# Tractive_System_Light_Control_Board.net
KiCad netlist of a schematic drawn in EAGLE
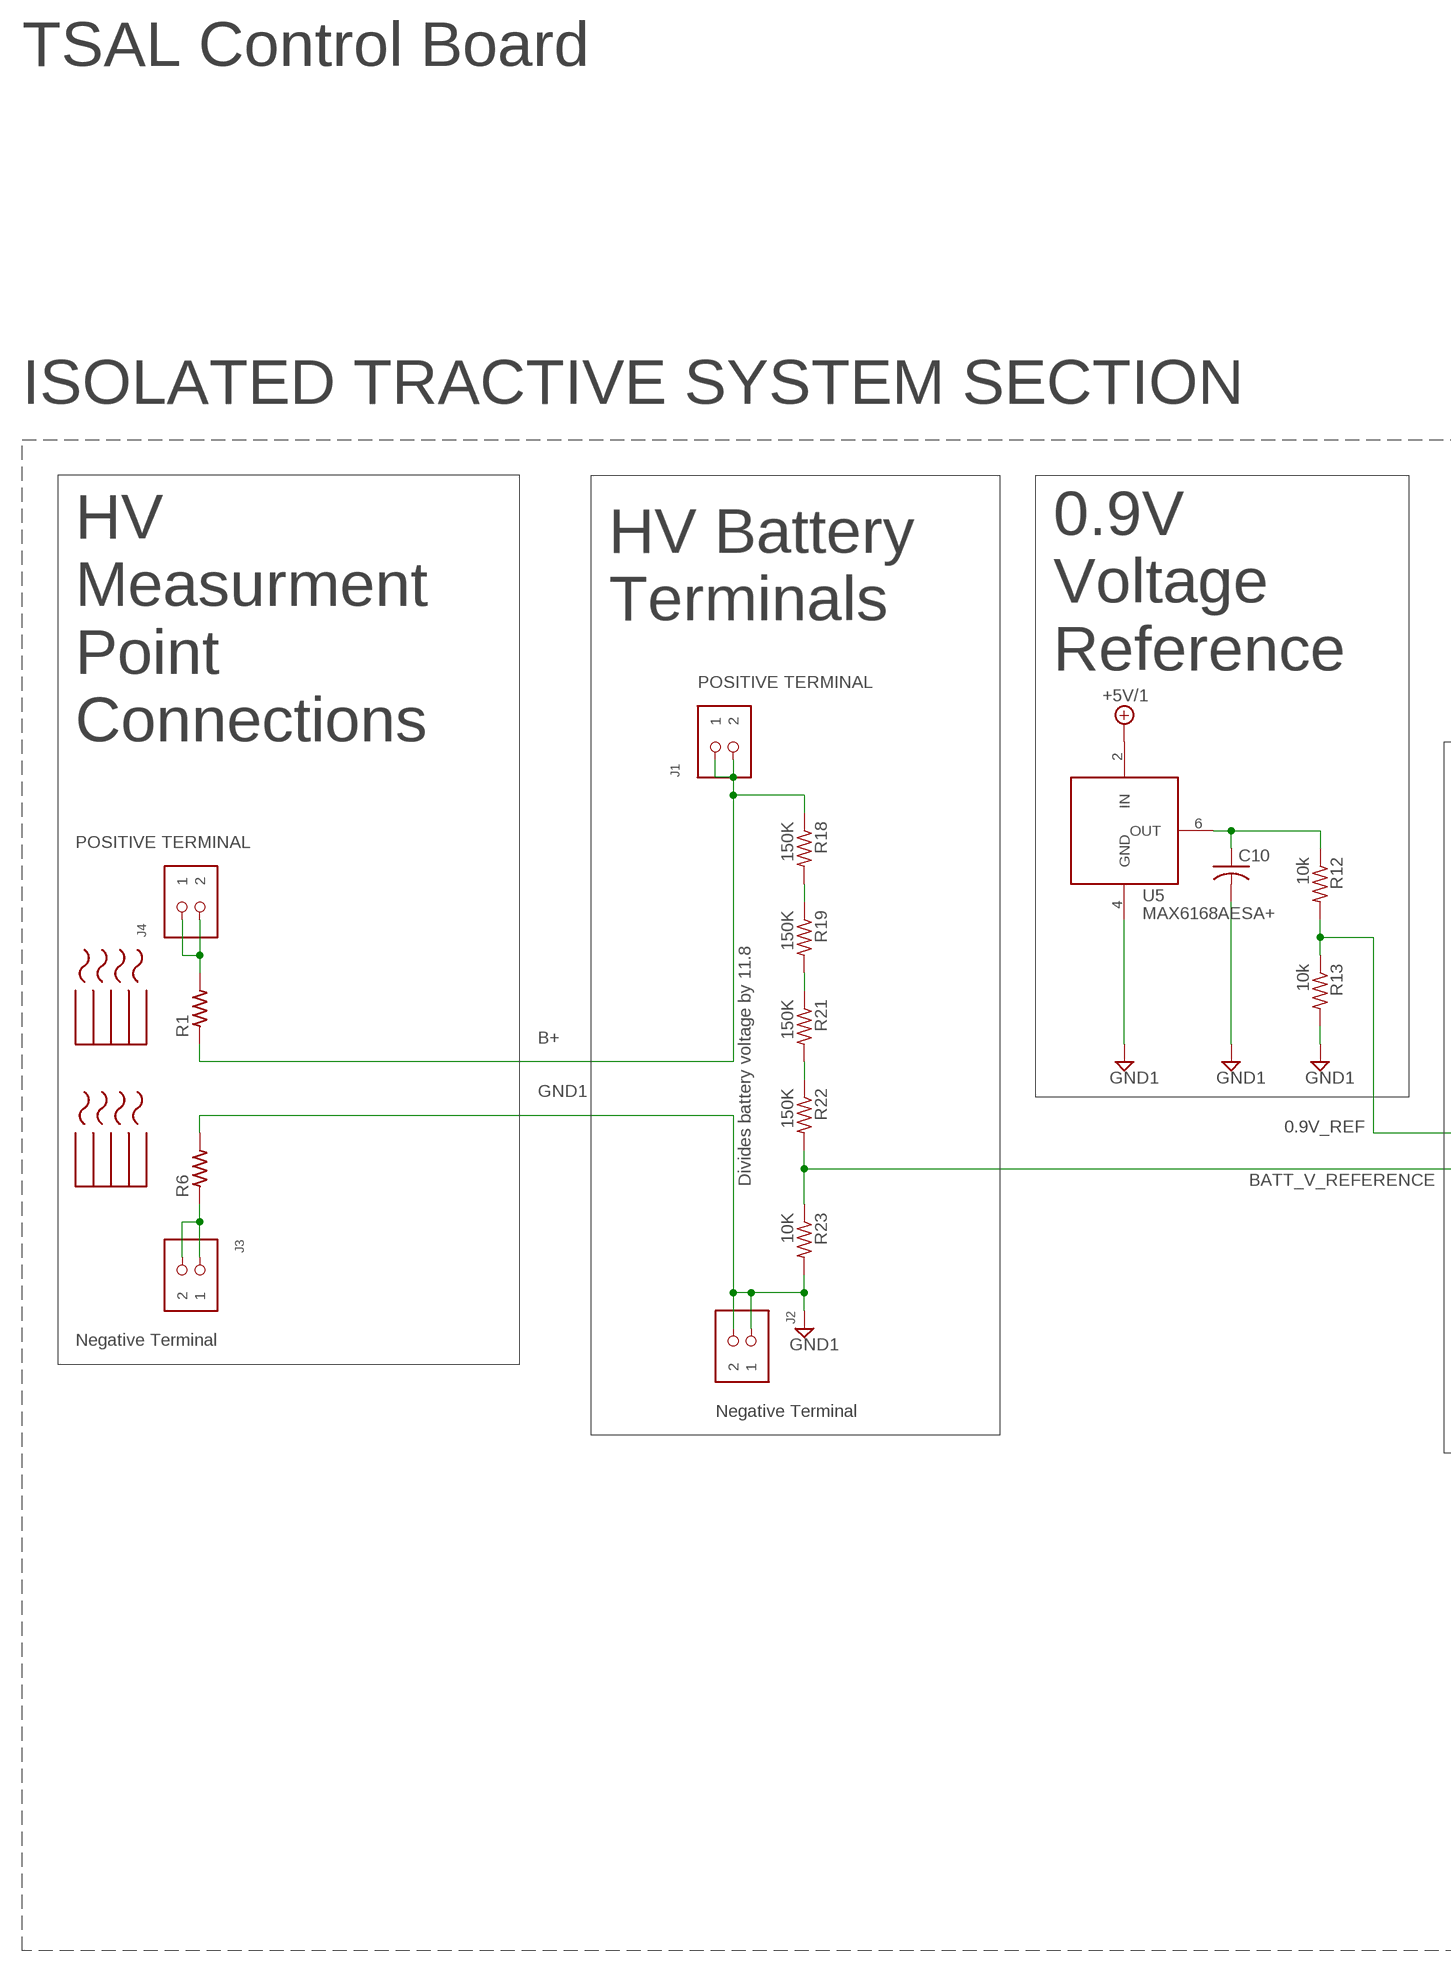
[diagram p0: schematic, sheet 1, part 1 of 2]
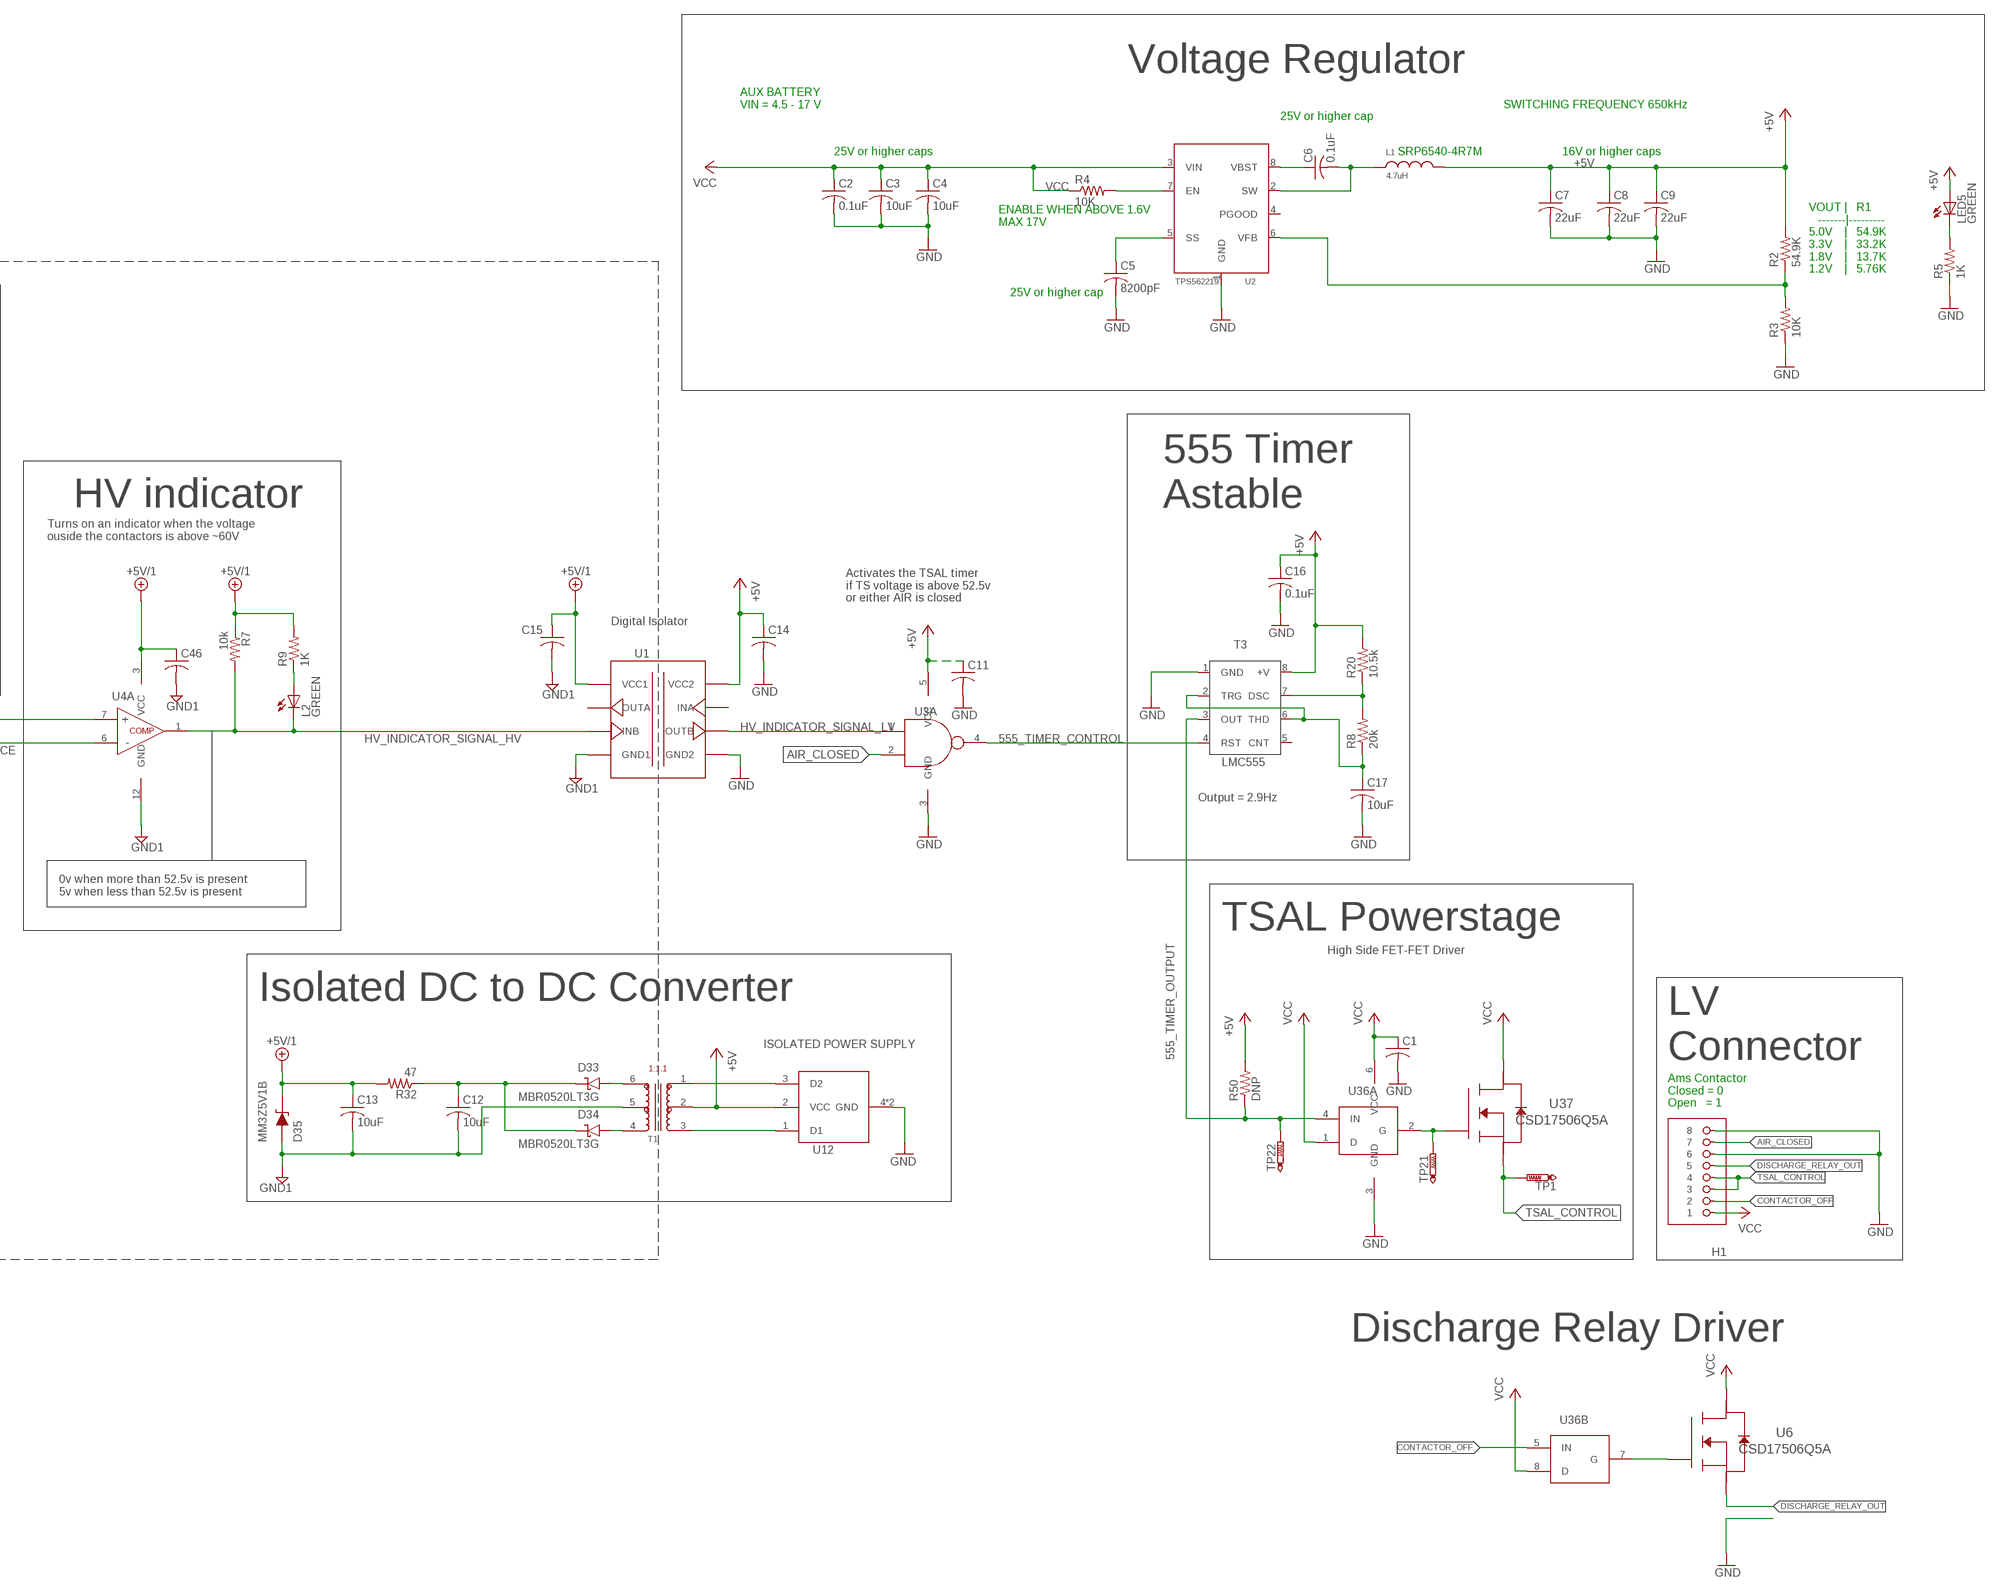
[diagram p1: schematic, sheet 1, part 2 of 2]

(export (version "E")
  (design (tool "Eeschema 10.0.6"))
  (components
    (comp (ref "C1")
      (value "0.1uF")
      (footprint "eagle-import:C0805")
      (fields (field (name "MPN") "C1005X7R1E104K050BB") (field (name "PARTNO") "GRM21BR71E104KA01L"))
      (libsource (lib "eagle-import") (part "rcl_C-USC0805"))
    )
    (comp (ref "C2")
      (value "0.1uF")
      (footprint "eagle-import:C0805")
      (fields (field (name "PARTNO") "GRM21BR71E104KA01L"))
      (libsource (lib "eagle-import") (part "C-USC0805"))
    )
    (comp (ref "C3")
      (value "10uF")
      (footprint "eagle-import:C0805")
      (fields (field (name "PARTNO") "GRM21BR61E106KA73L"))
      (libsource (lib "eagle-import") (part "C-USC0805"))
    )
    (comp (ref "C4")
      (value "10uF")
      (footprint "eagle-import:C0805")
      (fields (field (name "PARTNO") "GRM21BR61E106KA73L"))
      (libsource (lib "eagle-import") (part "C-USC0805"))
    )
    (comp (ref "C5")
      (value "8200pF")
      (footprint "eagle-import:C0805")
      (fields (field (name "PARTNO") "C0805C822K5RACTU"))
      (libsource (lib "eagle-import") (part "C-USC0805"))
    )
    (comp (ref "C6")
      (value "0.1uF")
      (footprint "eagle-import:C0805")
      (fields (field (name "PARTNO") "GRM21BR71E104KA01L"))
      (libsource (lib "eagle-import") (part "C-USC0805"))
    )
    (comp (ref "C7")
      (value "22uF")
      (footprint "eagle-import:C0805")
      (fields (field (name "PARTNO") "C2012JB1E226M125AC"))
      (libsource (lib "eagle-import") (part "C-USC0805"))
    )
    (comp (ref "C8")
      (value "22uF")
      (footprint "eagle-import:C0805")
      (fields (field (name "PARTNO") "C2012JB1E226M125AC"))
      (libsource (lib "eagle-import") (part "C-USC0805"))
    )
    (comp (ref "C9")
      (value "22uF")
      (footprint "eagle-import:C0805")
      (fields (field (name "PARTNO") "C2012JB1E226M125AC"))
      (libsource (lib "eagle-import") (part "C-USC0805"))
    )
    (comp (ref "C10")
      (value "0.1uF")
      (footprint "eagle-import:C0805")
      (fields (field (name "MPN") "C1005X7R1E104K050BB") (field (name "PARTNO") "GRM21BR71E104KA01L"))
      (libsource (lib "eagle-import") (part "rcl_C-USC0805"))
    )
    (comp (ref "C11")
      (value "0.1uF")
      (footprint "eagle-import:C0805")
      (fields (field (name "MPN") "C1005X7R1E104K050BB") (field (name "PARTNO") "GRM21BR71E104KA01L"))
      (libsource (lib "eagle-import") (part "rcl_C-USC0805"))
    )
    (comp (ref "C12")
      (value "10uF")
      (footprint "eagle-import:C0805")
      (fields (field (name "MPN") "C1005X7R1E104K050BB") (field (name "PARTNO") "GRM21BR61E106KA73L"))
      (libsource (lib "eagle-import") (part "rcl_C-USC0805"))
    )
    (comp (ref "C13")
      (value "10uF")
      (footprint "eagle-import:C0805")
      (fields (field (name "MPN") "C1005X7R1E104K050BB") (field (name "PARTNO") "GRM21BR61E106KA73L"))
      (libsource (lib "eagle-import") (part "rcl_C-USC0805"))
    )
    (comp (ref "C14")
      (value "0.1uF")
      (footprint "eagle-import:C0805")
      (fields (field (name "MPN") "C1005X7R1E104K050BB") (field (name "PARTNO") "GRM21BR71E104KA01L"))
      (libsource (lib "eagle-import") (part "rcl_C-USC0805"))
    )
    (comp (ref "C15")
      (value "0.1uF")
      (footprint "eagle-import:C0805")
      (fields (field (name "MPN") "C1005X7R1E104K050BB") (field (name "PARTNO") "GRM21BR71E104KA01L"))
      (libsource (lib "eagle-import") (part "rcl_C-USC0805"))
    )
    (comp (ref "C16")
      (value "0.1uF")
      (footprint "eagle-import:C0805")
      (fields (field (name "PARTNO") "08053C104KAT2A"))
      (libsource (lib "eagle-import") (part "C-USC0805"))
    )
    (comp (ref "C17")
      (value "10uF")
      (footprint "eagle-import:C0805")
      (fields (field (name "PARTNO") "GRM21BR61E106KA73L"))
      (libsource (lib "eagle-import") (part "C-USC0805"))
    )
    (comp (ref "C46")
      (value "0.1uF")
      (footprint "eagle-import:C0805")
      (fields (field (name "MPN") "C1005X7R1E104K050BB") (field (name "PARTNO") "GRM21BR71E104KA01L"))
      (libsource (lib "eagle-import") (part "rcl_C-USC0805"))
    )
    (comp (ref "D33")
      (value "MBR0520LT3G")
      (footprint "eagle-import:SOD-123")
      (libsource (lib "eagle-import") (part "MBR0520LT3G"))
    )
    (comp (ref "D34")
      (value "MBR0520LT3G")
      (footprint "eagle-import:SOD-123")
      (libsource (lib "eagle-import") (part "MBR0520LT3G"))
    )
    (comp (ref "D35")
      (value "MM3Z5V1B")
      (footprint "eagle-import:SOD323F")
      (libsource (lib "eagle-import") (part "MM3Z5V1B"))
    )
    (comp (ref "H1")
      (value "MOLEX_CLIKMATE-8-VERTICAL-5025841170")
      (footprint "eagle-import:MOLEX-CLIKMATE-8-VERTICAL-HEADER")
      (fields (field (name "PARTNO") "5025840870"))
      (libsource (lib "eagle-import") (part "MOLEX_CLIKMATE-8-VERTICAL-5025841170"))
    )
    (comp (ref "J1")
      (value "MOLEX_CLICKMATE-2-VERTICAL")
      (footprint "eagle-import:MOLEX-CLIKMATE-2-VERTICAL-HEADER")
      (fields (field (name "PARTNO") "5025840270"))
      (libsource (lib "eagle-import") (part "MOLEX_CLICKMATE-2-VERTICAL"))
    )
    (comp (ref "J2")
      (value "MOLEX_CLICKMATE-2-VERTICAL")
      (footprint "eagle-import:MOLEX-CLIKMATE-2-VERTICAL-HEADER")
      (fields (field (name "PARTNO") "5025840270"))
      (libsource (lib "eagle-import") (part "MOLEX_CLICKMATE-2-VERTICAL"))
    )
    (comp (ref "J3")
      (value "MOLEX_CLICKMATE-2-VERTICAL")
      (footprint "eagle-import:MOLEX-CLIKMATE-2-VERTICAL-HEADER")
      (fields (field (name "PARTNO") "5025840270"))
      (libsource (lib "eagle-import") (part "MOLEX_CLICKMATE-2-VERTICAL"))
    )
    (comp (ref "J4")
      (value "MOLEX_CLICKMATE-2-VERTICAL")
      (footprint "eagle-import:MOLEX-CLIKMATE-2-VERTICAL-HEADER")
      (fields (field (name "PARTNO") "5025840270"))
      (libsource (lib "eagle-import") (part "MOLEX_CLICKMATE-2-VERTICAL"))
    )
    (comp (ref "L1")
      (value "4.7uH")
      (footprint "eagle-import:SRP6540")
      (fields (field (name "PARTNO") "SRP6540-4R7M"))
      (libsource (lib "eagle-import") (part "SRP6540"))
    )
    (comp (ref "L2")
      (value "GREEN")
      (footprint "eagle-import:CHIPLED_0805")
      (fields (field (name "PARTNO") "598-8170-107F"))
      (libsource (lib "eagle-import") (part "LEDCHIPLED_0805"))
    )
    (comp (ref "LED5")
      (value "GREEN")
      (footprint "eagle-import:CHIPLED_0805")
      (fields (field (name "PARTNO") "598-8170-107F"))
      (libsource (lib "eagle-import") (part "LEDCHIPLED_0805"))
    )
    (comp (ref "R1")
      (value "RTO020F10001JTE3")
      (footprint "eagle-import:TO-220-2")
      (libsource (lib "eagle-import") (part "RTO020F10001JTE3"))
    )
    (comp (ref "R2")
      (value "54.9K")
      (footprint "eagle-import:R0805")
      (fields (field (name "PARTNO") "ERA-6AEB5492V"))
      (libsource (lib "eagle-import") (part "R-US_R0805"))
    )
    (comp (ref "R3")
      (value "10K")
      (footprint "eagle-import:R0805")
      (fields (field (name "PARTNO") "ERJ-6ENF1002V"))
      (libsource (lib "eagle-import") (part "R-US_R0805"))
    )
    (comp (ref "R4")
      (value "10K")
      (footprint "eagle-import:R0805")
      (fields (field (name "PARTNO") "ERJ-6ENF1002V"))
      (libsource (lib "eagle-import") (part "R-US_R0805"))
    )
    (comp (ref "R5")
      (value "1K")
      (footprint "eagle-import:R0805")
      (fields (field (name "PARTNO") "ERJ-6ENF1001V"))
      (libsource (lib "eagle-import") (part "R-US_R0805"))
    )
    (comp (ref "R6")
      (value "RTO020F10001JTE3")
      (footprint "eagle-import:TO-220-2")
      (libsource (lib "eagle-import") (part "RTO020F10001JTE3"))
    )
    (comp (ref "R7")
      (value "10k")
      (footprint "eagle-import:R0805")
      (fields (field (name "PARTNO") "ERJ-6ENF1002V"))
      (libsource (lib "eagle-import") (part "R-US_R0805"))
    )
    (comp (ref "R8")
      (value "20k")
      (footprint "eagle-import:R0805")
      (fields (field (name "PARTNO") "ERJ-6ENF2002V"))
      (libsource (lib "eagle-import") (part "R-US_R0805"))
    )
    (comp (ref "R9")
      (value "1K")
      (footprint "eagle-import:R0805")
      (fields (field (name "PARTNO") "ERJ-6ENF1001V"))
      (libsource (lib "eagle-import") (part "R-US_R0805"))
    )
    (comp (ref "R12")
      (value "10k")
      (footprint "eagle-import:R0805")
      (fields (field (name "PARTNO") "ERJ-6ENF1002V"))
      (libsource (lib "eagle-import") (part "R-US_R0805"))
    )
    (comp (ref "R13")
      (value "10k")
      (footprint "eagle-import:R0805")
      (fields (field (name "PARTNO") "ERJ-6ENF1002V"))
      (libsource (lib "eagle-import") (part "R-US_R0805"))
    )
    (comp (ref "R18")
      (value "150K")
      (footprint "eagle-import:R0805")
      (fields (field (name "PARTNO") "ERJ-6ENF1503V"))
      (libsource (lib "eagle-import") (part "R-US_R0805"))
    )
    (comp (ref "R19")
      (value "150K")
      (footprint "eagle-import:R0805")
      (fields (field (name "PARTNO") "ERJ-6ENF1503V"))
      (libsource (lib "eagle-import") (part "R-US_R0805"))
    )
    (comp (ref "R20")
      (value "10.5k")
      (footprint "eagle-import:R0805")
      (fields (field (name "PARTNO") "ERJ-6ENF1052V"))
      (libsource (lib "eagle-import") (part "R-US_R0805"))
    )
    (comp (ref "R21")
      (value "150K")
      (footprint "eagle-import:R0805")
      (fields (field (name "PARTNO") "ERJ-6ENF1503V"))
      (libsource (lib "eagle-import") (part "R-US_R0805"))
    )
    (comp (ref "R22")
      (value "150K")
      (footprint "eagle-import:R0805")
      (fields (field (name "PARTNO") "ERJ-6ENF1503V"))
      (libsource (lib "eagle-import") (part "R-US_R0805"))
    )
    (comp (ref "R23")
      (value "10K")
      (footprint "eagle-import:R0805")
      (fields (field (name "PARTNO") "ERJ-6ENF1002V"))
      (libsource (lib "eagle-import") (part "R-US_R0805"))
    )
    (comp (ref "R32")
      (value "47")
      (footprint "eagle-import:R0805")
      (fields (field (name "PARTNO") "ERA-6AEB470V"))
      (libsource (lib "eagle-import") (part "rcl_R-US_R0805"))
    )
    (comp (ref "R50")
      (value "DNP")
      (footprint "eagle-import:R0805")
      (libsource (lib "eagle-import") (part "rcl_R-US_R0805"))
    )
    (comp (ref "T1")
      (value "750313734")
      (footprint "eagle-import:WURTH-750313734")
      (libsource (lib "eagle-import") (part "WURTH-750313734"))
    )
    (comp (ref "T3")
      (value "LMC555")
      (footprint "eagle-import:LMC555")
      (fields (field (name "PARTNO") "LMC555CMM/NOPB"))
      (libsource (lib "eagle-import") (part "LMC555DGK"))
    )
    (comp (ref "TP1")
      (value "PTR1TP20R")
      (footprint "eagle-import:TP20R")
      (libsource (lib "eagle-import") (part "PTR1TP20R"))
    )
    (comp (ref "TP21")
      (value "PTR1TP20R")
      (footprint "eagle-import:TP20R")
      (libsource (lib "eagle-import") (part "PTR1TP20R"))
    )
    (comp (ref "TP22")
      (value "PTR1TP20R")
      (footprint "eagle-import:TP20R")
      (libsource (lib "eagle-import") (part "PTR1TP20R"))
    )
    (comp (ref "U$1")
      (value "581002B02500G")
      (footprint "eagle-import:AAVID-581X")
      (libsource (lib "eagle-import") (part "AAVID-581X"))
    )
    (comp (ref "U$2")
      (value "581002B02500G")
      (footprint "eagle-import:AAVID-581X")
      (libsource (lib "eagle-import") (part "AAVID-581X"))
    )
    (comp (ref "U1")
      (value "ISO7221")
      (footprint "eagle-import:ISO722X")
      (fields (field (name "PARTNO") "ISO7221CDR"))
      (libsource (lib "eagle-import") (part "ISO7221"))
    )
    (comp (ref "U2")
      (value "TPS562219")
      (footprint "eagle-import:TPS562219")
      (fields (field (name "PARTNO") "TPS562219DDFT"))
      (libsource (lib "eagle-import") (part "TPS562219"))
    )
    (comp (ref "U3")
      (value "SN74LVC1G00DRL")
      (footprint "eagle-import:LITTLE_LOGIC_BASIC_DRL")
      (fields (field (name "PARTNO") "SN74LVC1G00DRLR"))
      (libsource (lib "eagle-import") (part "LL_NAND{colon}SN74LVC1G00DRL"))
    )
    (comp (ref "U4")
      (value "LM139")
      (footprint "eagle-import:D14")
      (fields (field (name "MANUFACTURER") "Texas Instruments") (field (name "PARTNO") "LM139DR"))
      (libsource (lib "eagle-import") (part "LM139"))
    )
    (comp (ref "U5")
      (value "MAX6168AESA+")
      (footprint "eagle-import:SOIC-8")
      (libsource (lib "eagle-import") (part "MAX616X"))
    )
    (comp (ref "U6")
      (value "CSD17506Q5A")
      (footprint "eagle-import:SON_5X6")
      (libsource (lib "eagle-import") (part "CSD17506Q5A"))
    )
    (comp (ref "U12")
      (value "SN6501DBVR")
      (footprint "eagle-import:SN6501DBV")
      (libsource (lib "eagle-import") (part "SN6501"))
    )
    (comp (ref "U36")
      (value "LTC1155")
      (footprint "eagle-import:LT-SOL8")
      (fields (field (name "PARTNO") "LTC1155CS8#PBF"))
      (libsource (lib "eagle-import") (part "LTC1155"))
    )
    (comp (ref "U37")
      (value "CSD17506Q5A")
      (footprint "eagle-import:SON_5X6")
      (libsource (lib "eagle-import") (part "CSD17506Q5A"))
    )
  )
  (nets
    (net (code "1") (name "+5V") (class "Default")
      (node (ref "C11") (pin "1") (pinfunction "1_1") (pintype "passive"))
      (node (ref "C14") (pin "1") (pinfunction "1_1") (pintype "passive"))
      (node (ref "C16") (pin "1") (pinfunction "1_1") (pintype "passive"))
      (node (ref "C7") (pin "1") (pinfunction "1_1") (pintype "passive"))
      (node (ref "C8") (pin "1") (pinfunction "1_1") (pintype "passive"))
      (node (ref "C9") (pin "1") (pinfunction "1_1") (pintype "passive"))
      (node (ref "L1") (pin "P$2") (pinfunction "P$2_P$2") (pintype "bidirectional"))
      (node (ref "LED5") (pin "A") (pinfunction "A_A") (pintype "passive"))
      (node (ref "R2") (pin "2") (pinfunction "2_2") (pintype "passive"))
      (node (ref "R20") (pin "2") (pinfunction "2_2") (pintype "passive"))
      (node (ref "R50") (pin "2") (pinfunction "2_2") (pintype "passive"))
      (node (ref "T1") (pin "2") (pinfunction "2_2") (pintype "bidirectional"))
      (node (ref "T3") (pin "8") (pinfunction "+V_8") (pintype "bidirectional"))
      (node (ref "U1") (pin "P$8") (pinfunction "VCC2_P$8") (pintype "bidirectional"))
      (node (ref "U12") (pin "2") (pinfunction "VCC_2") (pintype "bidirectional"))
      (node (ref "U3") (pin "5") (pinfunction "VCC_5") (pintype "power_in"))
    )
    (net (code "2") (name "+5V{slash}1") (class "Default")
      (node (ref "C13") (pin "1") (pinfunction "1_1") (pintype "passive"))
      (node (ref "C15") (pin "1") (pinfunction "1_1") (pintype "passive"))
      (node (ref "C46") (pin "1") (pinfunction "1_1") (pintype "passive"))
      (node (ref "D35") (pin "CATHODE") (pinfunction "CATHODE_CATHODE") (pintype "bidirectional"))
      (node (ref "R32") (pin "2") (pinfunction "2_2") (pintype "passive"))
      (node (ref "R7") (pin "1") (pinfunction "1_1") (pintype "passive"))
      (node (ref "R9") (pin "2") (pinfunction "2_2") (pintype "passive"))
      (node (ref "U1") (pin "P$1") (pinfunction "VCC1_P$1") (pintype "bidirectional"))
      (node (ref "U4") (pin "3") (pinfunction "VCC_3") (pintype "power_in"))
      (node (ref "U5") (pin "2") (pinfunction "IN_2") (pintype "bidirectional"))
    )
    (net (code "3") (name "/0.9V_REF") (class "Default")
      (node (ref "R12") (pin "2") (pinfunction "2_2") (pintype "passive"))
      (node (ref "R13") (pin "1") (pinfunction "1_1") (pintype "passive"))
      (node (ref "U4") (pin "7") (pinfunction "+_7") (pintype "input"))
    )
    (net (code "4") (name "/555_TIMER_CONTROL") (class "Default")
      (node (ref "T3") (pin "4") (pinfunction "RST_4") (pintype "bidirectional"))
      (node (ref "U3") (pin "4") (pinfunction "OUT_4") (pintype "output"))
    )
    (net (code "5") (name "/555_TIMER_OUTPUT") (class "Default")
      (node (ref "R50") (pin "1") (pinfunction "1_1") (pintype "passive"))
      (node (ref "T3") (pin "3") (pinfunction "OUT_3") (pintype "bidirectional"))
      (node (ref "TP22") (pin "TP") (pinfunction "TP_TP") (pintype "input"))
      (node (ref "U36") (pin "4") (pinfunction "IN_4") (pintype "input"))
    )
    (net (code "6") (name "/B+") (class "Default")
      (node (ref "J1") (pin "1") (pinfunction "1_1") (pintype "bidirectional"))
      (node (ref "J1") (pin "2") (pinfunction "2_2") (pintype "bidirectional"))
      (node (ref "R1") (pin "P$1") (pinfunction "P$1_P$1") (pintype "bidirectional"))
      (node (ref "R18") (pin "1") (pinfunction "1_1") (pintype "passive"))
    )
    (net (code "7") (name "/BATT_V_REFERENCE") (class "Default")
      (node (ref "R22") (pin "2") (pinfunction "2_2") (pintype "passive"))
      (node (ref "R23") (pin "1") (pinfunction "1_1") (pintype "passive"))
      (node (ref "U4") (pin "6") (pinfunction "-_6") (pintype "input"))
    )
    (net (code "8") (name "/HV_INDICATOR_SIGNAL_HV") (class "Default")
      (node (ref "L2") (pin "C") (pinfunction "C_C") (pintype "passive"))
      (node (ref "R7") (pin "2") (pinfunction "2_2") (pintype "passive"))
      (node (ref "U1") (pin "P$3") (pinfunction "INB_P$3") (pintype "bidirectional"))
      (node (ref "U4") (pin "1") (pinfunction "OUT_1") (pintype "output"))
    )
    (net (code "9") (name "/HV_INDICATOR_SIGNAL_LV") (class "Default")
      (node (ref "U1") (pin "P$6") (pinfunction "OUTB_P$6") (pintype "bidirectional"))
      (node (ref "U3") (pin "1") (pinfunction "IN1_1") (pintype "input"))
    )
    (net (code "10") (name "AIR_CLOSED") (class "Default")
      (node (ref "H1") (pin "7") (pinfunction "7_7") (pintype "bidirectional"))
      (node (ref "U3") (pin "2") (pinfunction "IN2_2") (pintype "input"))
    )
    (net (code "11") (name "CONTACTOR_OFF") (class "Default")
      (node (ref "H1") (pin "2") (pinfunction "2_2") (pintype "bidirectional"))
      (node (ref "U36") (pin "5") (pinfunction "IN_5") (pintype "input"))
    )
    (net (code "12") (name "DISCHARGE_RELAY_OUT") (class "Default")
      (node (ref "H1") (pin "5") (pinfunction "5_5") (pintype "bidirectional"))
      (node (ref "U6") (pin "1") (pinfunction "S_1") (pintype "bidirectional"))
      (node (ref "U6") (pin "2") (pinfunction "S_2") (pintype "bidirectional"))
      (node (ref "U6") (pin "3") (pinfunction "S_3") (pintype "bidirectional"))
    )
    (net (code "13") (name "GND") (class "Default")
      (node (ref "C1") (pin "2") (pinfunction "2_2") (pintype "passive"))
      (node (ref "C11") (pin "2") (pinfunction "2_2") (pintype "passive"))
      (node (ref "C14") (pin "2") (pinfunction "2_2") (pintype "passive"))
      (node (ref "C16") (pin "2") (pinfunction "2_2") (pintype "passive"))
      (node (ref "C17") (pin "2") (pinfunction "2_2") (pintype "passive"))
      (node (ref "C2") (pin "2") (pinfunction "2_2") (pintype "passive"))
      (node (ref "C3") (pin "2") (pinfunction "2_2") (pintype "passive"))
      (node (ref "C4") (pin "2") (pinfunction "2_2") (pintype "passive"))
      (node (ref "C5") (pin "2") (pinfunction "2_2") (pintype "passive"))
      (node (ref "C7") (pin "2") (pinfunction "2_2") (pintype "passive"))
      (node (ref "C8") (pin "2") (pinfunction "2_2") (pintype "passive"))
      (node (ref "C9") (pin "2") (pinfunction "2_2") (pintype "passive"))
      (node (ref "H1") (pin "6") (pinfunction "6_6") (pintype "bidirectional"))
      (node (ref "H1") (pin "8") (pinfunction "8_8") (pintype "bidirectional"))
      (node (ref "R3") (pin "1") (pinfunction "1_1") (pintype "passive"))
      (node (ref "R5") (pin "1") (pinfunction "1_1") (pintype "passive"))
      (node (ref "T3") (pin "1") (pinfunction "GND_1") (pintype "bidirectional"))
      (node (ref "U1") (pin "P$5") (pinfunction "GND2_P$5") (pintype "bidirectional"))
      (node (ref "U12") (pin "4") (pinfunction "GND_4") (pintype "bidirectional"))
      (node (ref "U12") (pin "5") (pinfunction "GND_5") (pintype "bidirectional"))
      (node (ref "U2") (pin "1") (pinfunction "GND_1") (pintype "bidirectional"))
      (node (ref "U3") (pin "3") (pinfunction "GND_3") (pintype "power_in"))
      (node (ref "U36") (pin "3") (pinfunction "GND_3") (pintype "power_in"))
    )
    (net (code "14") (name "GND1") (class "Default")
      (node (ref "C10") (pin "2") (pinfunction "2_2") (pintype "passive"))
      (node (ref "C12") (pin "2") (pinfunction "2_2") (pintype "passive"))
      (node (ref "C13") (pin "2") (pinfunction "2_2") (pintype "passive"))
      (node (ref "C15") (pin "2") (pinfunction "2_2") (pintype "passive"))
      (node (ref "C46") (pin "2") (pinfunction "2_2") (pintype "passive"))
      (node (ref "D35") (pin "ANODE") (pinfunction "ANODE_ANODE") (pintype "bidirectional"))
      (node (ref "J2") (pin "1") (pinfunction "1_1") (pintype "bidirectional"))
      (node (ref "J2") (pin "2") (pinfunction "2_2") (pintype "bidirectional"))
      (node (ref "R13") (pin "2") (pinfunction "2_2") (pintype "passive"))
      (node (ref "R23") (pin "2") (pinfunction "2_2") (pintype "passive"))
      (node (ref "R6") (pin "P$2") (pinfunction "P$2_P$2") (pintype "bidirectional"))
      (node (ref "T1") (pin "5") (pinfunction "5_5") (pintype "bidirectional"))
      (node (ref "U1") (pin "P$4") (pinfunction "GND1_P$4") (pintype "bidirectional"))
      (node (ref "U4") (pin "12") (pinfunction "GND_12") (pintype "power_in"))
      (node (ref "U5") (pin "4") (pinfunction "GND_4") (pintype "bidirectional"))
    )
    (net (code "15") (name "Net-(C12-Pad1)") (class "Default")
      (node (ref "C12") (pin "1") (pinfunction "1_1") (pintype "passive"))
      (node (ref "D33") (pin "K") (pinfunction "K_K") (pintype "bidirectional"))
      (node (ref "D34") (pin "K") (pinfunction "K_K") (pintype "bidirectional"))
      (node (ref "R32") (pin "1") (pinfunction "1_1") (pintype "passive"))
    )
    (net (code "16") (name "Net-(D33-PadA)") (class "Default")
      (node (ref "D33") (pin "A") (pinfunction "A_A") (pintype "bidirectional"))
      (node (ref "T1") (pin "6") (pinfunction "6_6") (pintype "bidirectional"))
    )
    (net (code "17") (name "Net-(D34-PadA)") (class "Default")
      (node (ref "D34") (pin "A") (pinfunction "A_A") (pintype "bidirectional"))
      (node (ref "T1") (pin "4") (pinfunction "4_4") (pintype "bidirectional"))
    )
    (net (code "18") (name "Net-(J3-Pad1)") (class "Default")
      (node (ref "J3") (pin "1") (pinfunction "1_1") (pintype "bidirectional"))
      (node (ref "J3") (pin "2") (pinfunction "2_2") (pintype "bidirectional"))
      (node (ref "R6") (pin "P$1") (pinfunction "P$1_P$1") (pintype "bidirectional"))
    )
    (net (code "19") (name "Net-(J4-Pad1)") (class "Default")
      (node (ref "J4") (pin "1") (pinfunction "1_1") (pintype "bidirectional"))
      (node (ref "J4") (pin "2") (pinfunction "2_2") (pintype "bidirectional"))
      (node (ref "R1") (pin "P$2") (pinfunction "P$2_P$2") (pintype "bidirectional"))
    )
    (net (code "20") (name "Net-(L2-PadA)") (class "Default")
      (node (ref "L2") (pin "A") (pinfunction "A_A") (pintype "passive"))
      (node (ref "R9") (pin "1") (pinfunction "1_1") (pintype "passive"))
    )
    (net (code "21") (name "Net-(LED5-PadC)") (class "Default")
      (node (ref "LED5") (pin "C") (pinfunction "C_C") (pintype "passive"))
      (node (ref "R5") (pin "2") (pinfunction "2_2") (pintype "passive"))
    )
    (net (code "22") (name "Net-(R18-Pad2)") (class "Default")
      (node (ref "R18") (pin "2") (pinfunction "2_2") (pintype "passive"))
      (node (ref "R19") (pin "1") (pinfunction "1_1") (pintype "passive"))
    )
    (net (code "23") (name "Net-(R19-Pad2)") (class "Default")
      (node (ref "R19") (pin "2") (pinfunction "2_2") (pintype "passive"))
      (node (ref "R21") (pin "1") (pinfunction "1_1") (pintype "passive"))
    )
    (net (code "24") (name "Net-(R21-Pad2)") (class "Default")
      (node (ref "R21") (pin "2") (pinfunction "2_2") (pintype "passive"))
      (node (ref "R22") (pin "1") (pinfunction "1_1") (pintype "passive"))
    )
    (net (code "25") (name "Net-(T3-DSC)") (class "Default")
      (node (ref "R20") (pin "1") (pinfunction "1_1") (pintype "passive"))
      (node (ref "R8") (pin "2") (pinfunction "2_2") (pintype "passive"))
      (node (ref "T3") (pin "7") (pinfunction "DSC_7") (pintype "bidirectional"))
    )
    (net (code "26") (name "Net-(T3-THD)") (class "Default")
      (node (ref "C17") (pin "1") (pinfunction "1_1") (pintype "passive"))
      (node (ref "R8") (pin "1") (pinfunction "1_1") (pintype "passive"))
      (node (ref "T3") (pin "2") (pinfunction "TRG_2") (pintype "bidirectional"))
      (node (ref "T3") (pin "6") (pinfunction "THD_6") (pintype "bidirectional"))
    )
    (net (code "27") (name "Net-(U2-EN)") (class "Default")
      (node (ref "R4") (pin "2") (pinfunction "2_2") (pintype "passive"))
      (node (ref "U2") (pin "7") (pinfunction "EN_7") (pintype "bidirectional"))
    )
    (net (code "28") (name "Net-(U2-SS)") (class "Default")
      (node (ref "C5") (pin "1") (pinfunction "1_1") (pintype "passive"))
      (node (ref "U2") (pin "5") (pinfunction "SS_5") (pintype "bidirectional"))
    )
    (net (code "29") (name "Net-(U2-SW)") (class "Default")
      (node (ref "C6") (pin "2") (pinfunction "2_2") (pintype "passive"))
      (node (ref "L1") (pin "P$1") (pinfunction "P$1_P$1") (pintype "bidirectional"))
      (node (ref "U2") (pin "2") (pinfunction "SW_2") (pintype "bidirectional"))
    )
    (net (code "30") (name "Net-(U2-VBST)") (class "Default")
      (node (ref "C6") (pin "1") (pinfunction "1_1") (pintype "passive"))
      (node (ref "U2") (pin "8") (pinfunction "VBST_8") (pintype "bidirectional"))
    )
    (net (code "31") (name "Net-(U2-VFB)") (class "Default")
      (node (ref "R2") (pin "1") (pinfunction "1_1") (pintype "passive"))
      (node (ref "R3") (pin "2") (pinfunction "2_2") (pintype "passive"))
      (node (ref "U2") (pin "6") (pinfunction "VFB_6") (pintype "bidirectional"))
    )
    (net (code "32") (name "Net-(U5-OUT)") (class "Default")
      (node (ref "C10") (pin "1") (pinfunction "1_1") (pintype "passive"))
      (node (ref "R12") (pin "1") (pinfunction "1_1") (pintype "passive"))
      (node (ref "U5") (pin "6") (pinfunction "OUT_6") (pintype "bidirectional"))
    )
    (net (code "33") (name "Net-(U12-D1)") (class "Default")
      (node (ref "T1") (pin "3") (pinfunction "3_3") (pintype "bidirectional"))
      (node (ref "U12") (pin "1") (pinfunction "D1_1") (pintype "bidirectional"))
    )
    (net (code "34") (name "Net-(U12-D2)") (class "Default")
      (node (ref "T1") (pin "1") (pinfunction "1_1") (pintype "bidirectional"))
      (node (ref "U12") (pin "3") (pinfunction "D2_3") (pintype "bidirectional"))
    )
    (net (code "35") (name "Net-(U36A-G)") (class "Default")
      (node (ref "TP21") (pin "TP") (pinfunction "TP_TP") (pintype "input"))
      (node (ref "U36") (pin "2") (pinfunction "G_2") (pintype "output"))
      (node (ref "U37") (pin "4") (pinfunction "G_4") (pintype "input"))
    )
    (net (code "36") (name "Net-(U36B-G)") (class "Default")
      (node (ref "U36") (pin "7") (pinfunction "G_7") (pintype "output"))
      (node (ref "U6") (pin "4") (pinfunction "G_4") (pintype "input"))
    )
    (net (code "37") (name "TSAL_CONTROL") (class "Default")
      (node (ref "H1") (pin "3") (pinfunction "3_3") (pintype "bidirectional"))
      (node (ref "H1") (pin "4") (pinfunction "4_4") (pintype "bidirectional"))
      (node (ref "TP1") (pin "TP") (pinfunction "TP_TP") (pintype "input"))
      (node (ref "U37") (pin "1") (pinfunction "S_1") (pintype "bidirectional"))
      (node (ref "U37") (pin "2") (pinfunction "S_2") (pintype "bidirectional"))
      (node (ref "U37") (pin "3") (pinfunction "S_3") (pintype "bidirectional"))
    )
    (net (code "38") (name "VCC") (class "Default")
      (node (ref "C1") (pin "1") (pinfunction "1_1") (pintype "passive"))
      (node (ref "C2") (pin "1") (pinfunction "1_1") (pintype "passive"))
      (node (ref "C3") (pin "1") (pinfunction "1_1") (pintype "passive"))
      (node (ref "C4") (pin "1") (pinfunction "1_1") (pintype "passive"))
      (node (ref "H1") (pin "1") (pinfunction "1_1") (pintype "bidirectional"))
      (node (ref "R4") (pin "1") (pinfunction "1_1") (pintype "passive"))
      (node (ref "U2") (pin "3") (pinfunction "VIN_3") (pintype "bidirectional"))
      (node (ref "U36") (pin "1") (pinfunction "D_1") (pintype "input"))
      (node (ref "U36") (pin "6") (pinfunction "VCC_6") (pintype "power_in"))
      (node (ref "U36") (pin "8") (pinfunction "D_8") (pintype "input"))
      (node (ref "U37") (pin "5") (pinfunction "D_5") (pintype "bidirectional"))
      (node (ref "U37") (pin "6") (pinfunction "D_6") (pintype "bidirectional"))
      (node (ref "U37") (pin "7") (pinfunction "D_7") (pintype "bidirectional"))
      (node (ref "U37") (pin "8") (pinfunction "D_8") (pintype "bidirectional"))
      (node (ref "U37") (pin "PAD") (pinfunction "D_PAD") (pintype "bidirectional"))
      (node (ref "U37") (pin "PAD1") (pinfunction "D_PAD1") (pintype "bidirectional"))
      (node (ref "U37") (pin "VIA1") (pinfunction "D_VIA1") (pintype "bidirectional"))
      (node (ref "U37") (pin "VIA2") (pinfunction "D_VIA2") (pintype "bidirectional"))
      (node (ref "U37") (pin "VIA3") (pinfunction "D_VIA3") (pintype "bidirectional"))
      (node (ref "U37") (pin "VIA4") (pinfunction "D_VIA4") (pintype "bidirectional"))
      (node (ref "U37") (pin "VIA5") (pinfunction "D_VIA5") (pintype "bidirectional"))
      (node (ref "U37") (pin "VIA6") (pinfunction "D_VIA6") (pintype "bidirectional"))
      (node (ref "U37") (pin "VIA7") (pinfunction "D_VIA7") (pintype "bidirectional"))
      (node (ref "U37") (pin "VIA8") (pinfunction "D_VIA8") (pintype "bidirectional"))
      (node (ref "U37") (pin "VIA9") (pinfunction "D_VIA9") (pintype "bidirectional"))
      (node (ref "U6") (pin "5") (pinfunction "D_5") (pintype "bidirectional"))
      (node (ref "U6") (pin "6") (pinfunction "D_6") (pintype "bidirectional"))
      (node (ref "U6") (pin "7") (pinfunction "D_7") (pintype "bidirectional"))
      (node (ref "U6") (pin "8") (pinfunction "D_8") (pintype "bidirectional"))
      (node (ref "U6") (pin "PAD") (pinfunction "D_PAD") (pintype "bidirectional"))
      (node (ref "U6") (pin "PAD1") (pinfunction "D_PAD1") (pintype "bidirectional"))
      (node (ref "U6") (pin "VIA1") (pinfunction "D_VIA1") (pintype "bidirectional"))
      (node (ref "U6") (pin "VIA2") (pinfunction "D_VIA2") (pintype "bidirectional"))
      (node (ref "U6") (pin "VIA3") (pinfunction "D_VIA3") (pintype "bidirectional"))
      (node (ref "U6") (pin "VIA4") (pinfunction "D_VIA4") (pintype "bidirectional"))
      (node (ref "U6") (pin "VIA5") (pinfunction "D_VIA5") (pintype "bidirectional"))
      (node (ref "U6") (pin "VIA6") (pinfunction "D_VIA6") (pintype "bidirectional"))
      (node (ref "U6") (pin "VIA7") (pinfunction "D_VIA7") (pintype "bidirectional"))
      (node (ref "U6") (pin "VIA8") (pinfunction "D_VIA8") (pintype "bidirectional"))
      (node (ref "U6") (pin "VIA9") (pinfunction "D_VIA9") (pintype "bidirectional"))
    )
    (net (code "39") (name "unconnected-(T3-CNT-Pad5)") (class "Default")
      (node (ref "T3") (pin "5") (pinfunction "CNT_5") (pintype "bidirectional"))
    )
    (net (code "40") (name "unconnected-(U1-INA-PadP$7)") (class "Default")
      (node (ref "U1") (pin "P$7") (pinfunction "INA_P$7") (pintype "bidirectional"))
    )
    (net (code "41") (name "unconnected-(U1-OUTA-PadP$2)") (class "Default")
      (node (ref "U1") (pin "P$2") (pinfunction "OUTA_P$2") (pintype "bidirectional"))
    )
    (net (code "42") (name "unconnected-(U2-PGOOD-Pad4)") (class "Default")
      (node (ref "U2") (pin "4") (pinfunction "PGOOD_4") (pintype "bidirectional"))
    )
  )
)
